# Small_2.net
KiCad netlist of a schematic drawn in EAGLE
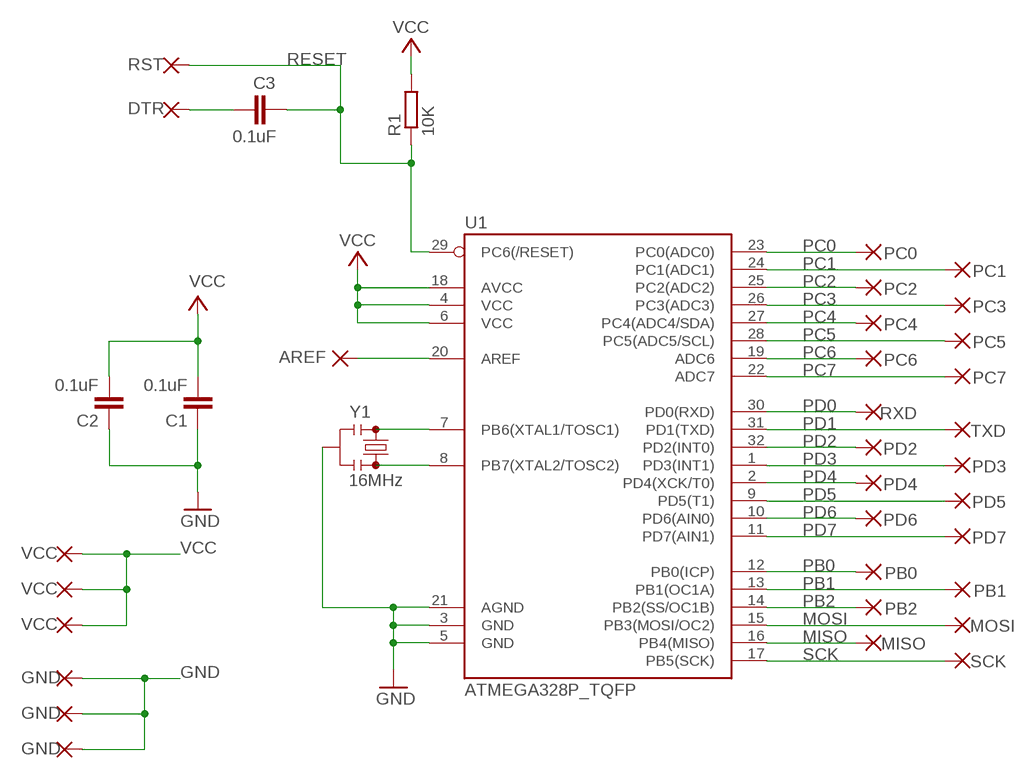
[diagram p0: schematic, sheet 1]

(export (version "E")
  (design (tool "Eeschema 10.0.6"))
  (components
    (comp (ref "AREF")
      (value "1,6/0,8")
      (footprint "eagle-import:1,6_0,8")
      (libsource (lib "eagle-import") (part "1,6/0,8"))
    )
    (comp (ref "C1")
      (value "0.1uF")
      (footprint "eagle-import:C0603")
      (libsource (lib "eagle-import") (part "C-EUC0603"))
    )
    (comp (ref "C2")
      (value "0.1uF")
      (footprint "eagle-import:C0603")
      (libsource (lib "eagle-import") (part "C-EUC0603"))
    )
    (comp (ref "C3")
      (value "0.1uF")
      (footprint "eagle-import:C0603")
      (libsource (lib "eagle-import") (part "C-EUC0603"))
    )
    (comp (ref "DTR")
      (value "1,6/0,8")
      (footprint "eagle-import:1,6_0,8")
      (libsource (lib "eagle-import") (part "1,6/0,8"))
    )
    (comp (ref "DTR1")
      (value "RST")
      (footprint "eagle-import:1,6_0,8")
      (libsource (lib "eagle-import") (part "1,6/0,8"))
    )
    (comp (ref "GND")
      (value "GND")
      (footprint "eagle-import:1,6_0,8")
      (libsource (lib "eagle-import") (part "1,6/0,8"))
    )
    (comp (ref "GND3")
      (value "GND")
      (footprint "eagle-import:1,6_0,8")
      (libsource (lib "eagle-import") (part "1,6/0,8"))
    )
    (comp (ref "GND4")
      (value "GND")
      (footprint "eagle-import:1,6_0,8")
      (libsource (lib "eagle-import") (part "1,6/0,8"))
    )
    (comp (ref "MISO")
      (value "MISO")
      (footprint "eagle-import:1,6_0,8")
      (libsource (lib "eagle-import") (part "1,6/0,8"))
    )
    (comp (ref "MOSI")
      (value "MOSI")
      (footprint "eagle-import:1,6_0,8")
      (libsource (lib "eagle-import") (part "1,6/0,8"))
    )
    (comp (ref "PB0")
      (value "1,6/0,8")
      (footprint "eagle-import:1,6_0,8")
      (libsource (lib "eagle-import") (part "1,6/0,8"))
    )
    (comp (ref "PB1")
      (value "1,6/0,8")
      (footprint "eagle-import:1,6_0,8")
      (libsource (lib "eagle-import") (part "1,6/0,8"))
    )
    (comp (ref "PB2")
      (value "1,6/0,8")
      (footprint "eagle-import:1,6_0,8")
      (libsource (lib "eagle-import") (part "1,6/0,8"))
    )
    (comp (ref "PC0")
      (value "1,6/0,8")
      (footprint "eagle-import:1,6_0,8")
      (libsource (lib "eagle-import") (part "1,6/0,8"))
    )
    (comp (ref "PC1")
      (value "1,6/0,8")
      (footprint "eagle-import:1,6_0,8")
      (libsource (lib "eagle-import") (part "1,6/0,8"))
    )
    (comp (ref "PC2")
      (value "1,6/0,8")
      (footprint "eagle-import:1,6_0,8")
      (libsource (lib "eagle-import") (part "1,6/0,8"))
    )
    (comp (ref "PC3")
      (value "1,6/0,8")
      (footprint "eagle-import:1,6_0,8")
      (libsource (lib "eagle-import") (part "1,6/0,8"))
    )
    (comp (ref "PC4")
      (value "1,6/0,8")
      (footprint "eagle-import:1,6_0,8")
      (libsource (lib "eagle-import") (part "1,6/0,8"))
    )
    (comp (ref "PC5")
      (value "1,6/0,8")
      (footprint "eagle-import:1,6_0,8")
      (libsource (lib "eagle-import") (part "1,6/0,8"))
    )
    (comp (ref "PC6")
      (value "1,6/0,8")
      (footprint "eagle-import:1,6_0,8")
      (libsource (lib "eagle-import") (part "1,6/0,8"))
    )
    (comp (ref "PC7")
      (value "1,6/0,8")
      (footprint "eagle-import:1,6_0,8")
      (libsource (lib "eagle-import") (part "1,6/0,8"))
    )
    (comp (ref "PD2")
      (value "1,6/0,8")
      (footprint "eagle-import:1,6_0,8")
      (libsource (lib "eagle-import") (part "1,6/0,8"))
    )
    (comp (ref "PD3")
      (value "1,6/0,8")
      (footprint "eagle-import:1,6_0,8")
      (libsource (lib "eagle-import") (part "1,6/0,8"))
    )
    (comp (ref "PD4")
      (value "1,6/0,8")
      (footprint "eagle-import:1,6_0,8")
      (libsource (lib "eagle-import") (part "1,6/0,8"))
    )
    (comp (ref "PD5")
      (value "1,6/0,8")
      (footprint "eagle-import:1,6_0,8")
      (libsource (lib "eagle-import") (part "1,6/0,8"))
    )
    (comp (ref "PD6")
      (value "1,6/0,8")
      (footprint "eagle-import:1,6_0,8")
      (libsource (lib "eagle-import") (part "1,6/0,8"))
    )
    (comp (ref "PD7")
      (value "1,6/0,8")
      (footprint "eagle-import:1,6_0,8")
      (libsource (lib "eagle-import") (part "1,6/0,8"))
    )
    (comp (ref "R1")
      (value "10K")
      (footprint "eagle-import:R0603")
      (libsource (lib "eagle-import") (part "R-EU_R0603"))
    )
    (comp (ref "RXD")
      (value "1,6/0,8")
      (footprint "eagle-import:1,6_0,8")
      (libsource (lib "eagle-import") (part "1,6/0,8"))
    )
    (comp (ref "SCK")
      (value "SCK")
      (footprint "eagle-import:1,6_0,8")
      (libsource (lib "eagle-import") (part "1,6/0,8"))
    )
    (comp (ref "TXD")
      (value "1,6/0,8")
      (footprint "eagle-import:1,6_0,8")
      (libsource (lib "eagle-import") (part "1,6/0,8"))
    )
    (comp (ref "U1")
      (value "ATMEGA328P_TQFP")
      (footprint "eagle-import:TQFP32-08")
      (libsource (lib "eagle-import") (part "ATMEGA328P_TQFP"))
    )
    (comp (ref "VCC")
      (value "VCC")
      (footprint "eagle-import:1,6_0,8")
      (libsource (lib "eagle-import") (part "1,6/0,8"))
    )
    (comp (ref "VCC1")
      (value "VCC")
      (footprint "eagle-import:1,6_0,8")
      (libsource (lib "eagle-import") (part "1,6/0,8"))
    )
    (comp (ref "VCC2")
      (value "VCC")
      (footprint "eagle-import:1,6_0,8")
      (libsource (lib "eagle-import") (part "1,6/0,8"))
    )
    (comp (ref "Y1")
      (value "16MHz")
      (footprint "eagle-import:RESONATOR-SMD-3.2X1.3")
      (libsource (lib "eagle-import") (part "RESONATOR-16MHZSMD_3.2X1.3"))
    )
  )
  (nets
    (net (code "1") (name "/MISO") (class "Default")
      (node (ref "MISO") (pin "1") (pinfunction "P_1") (pintype "passive"))
      (node (ref "U1") (pin "16") (pinfunction "PB4(MISO)_16") (pintype "bidirectional"))
    )
    (net (code "2") (name "/MOSI") (class "Default")
      (node (ref "MOSI") (pin "1") (pinfunction "P_1") (pintype "passive"))
      (node (ref "U1") (pin "15") (pinfunction "PB3(MOSI/OC2)_15") (pintype "bidirectional"))
    )
    (net (code "3") (name "/PB0") (class "Default")
      (node (ref "PB0") (pin "1") (pinfunction "P_1") (pintype "passive"))
      (node (ref "U1") (pin "12") (pinfunction "PB0(ICP)_12") (pintype "bidirectional"))
    )
    (net (code "4") (name "/PB1") (class "Default")
      (node (ref "PB1") (pin "1") (pinfunction "P_1") (pintype "passive"))
      (node (ref "U1") (pin "13") (pinfunction "PB1(OC1A)_13") (pintype "bidirectional"))
    )
    (net (code "5") (name "/PB2") (class "Default")
      (node (ref "PB2") (pin "1") (pinfunction "P_1") (pintype "passive"))
      (node (ref "U1") (pin "14") (pinfunction "PB2(SS/OC1B)_14") (pintype "bidirectional"))
    )
    (net (code "6") (name "/PC0") (class "Default")
      (node (ref "PC0") (pin "1") (pinfunction "P_1") (pintype "passive"))
      (node (ref "U1") (pin "23") (pinfunction "PC0(ADC0)_23") (pintype "bidirectional"))
    )
    (net (code "7") (name "/PC1") (class "Default")
      (node (ref "PC1") (pin "1") (pinfunction "P_1") (pintype "passive"))
      (node (ref "U1") (pin "24") (pinfunction "PC1(ADC1)_24") (pintype "bidirectional"))
    )
    (net (code "8") (name "/PC2") (class "Default")
      (node (ref "PC2") (pin "1") (pinfunction "P_1") (pintype "passive"))
      (node (ref "U1") (pin "25") (pinfunction "PC2(ADC2)_25") (pintype "bidirectional"))
    )
    (net (code "9") (name "/PC3") (class "Default")
      (node (ref "PC3") (pin "1") (pinfunction "P_1") (pintype "passive"))
      (node (ref "U1") (pin "26") (pinfunction "PC3(ADC3)_26") (pintype "bidirectional"))
    )
    (net (code "10") (name "/PC4") (class "Default")
      (node (ref "PC4") (pin "1") (pinfunction "P_1") (pintype "passive"))
      (node (ref "U1") (pin "27") (pinfunction "PC4(ADC4/SDA)_27") (pintype "bidirectional"))
    )
    (net (code "11") (name "/PC5") (class "Default")
      (node (ref "PC5") (pin "1") (pinfunction "P_1") (pintype "passive"))
      (node (ref "U1") (pin "28") (pinfunction "PC5(ADC5/SCL)_28") (pintype "bidirectional"))
    )
    (net (code "12") (name "/PC6") (class "Default")
      (node (ref "PC6") (pin "1") (pinfunction "P_1") (pintype "passive"))
      (node (ref "U1") (pin "19") (pinfunction "ADC6_19") (pintype "bidirectional"))
    )
    (net (code "13") (name "/PC7") (class "Default")
      (node (ref "PC7") (pin "1") (pinfunction "P_1") (pintype "passive"))
      (node (ref "U1") (pin "22") (pinfunction "ADC7_22") (pintype "bidirectional"))
    )
    (net (code "14") (name "/PD0") (class "Default")
      (node (ref "RXD") (pin "1") (pinfunction "P_1") (pintype "passive"))
      (node (ref "U1") (pin "30") (pinfunction "PD0(RXD)_30") (pintype "bidirectional"))
    )
    (net (code "15") (name "/PD1") (class "Default")
      (node (ref "TXD") (pin "1") (pinfunction "P_1") (pintype "passive"))
      (node (ref "U1") (pin "31") (pinfunction "PD1(TXD)_31") (pintype "bidirectional"))
    )
    (net (code "16") (name "/PD2") (class "Default")
      (node (ref "PD2") (pin "1") (pinfunction "P_1") (pintype "passive"))
      (node (ref "U1") (pin "32") (pinfunction "PD2(INT0)_32") (pintype "bidirectional"))
    )
    (net (code "17") (name "/PD3") (class "Default")
      (node (ref "PD3") (pin "1") (pinfunction "P_1") (pintype "passive"))
      (node (ref "U1") (pin "1") (pinfunction "PD3(INT1)_1") (pintype "bidirectional"))
    )
    (net (code "18") (name "/PD4") (class "Default")
      (node (ref "PD4") (pin "1") (pinfunction "P_1") (pintype "passive"))
      (node (ref "U1") (pin "2") (pinfunction "PD4(XCK/T0)_2") (pintype "bidirectional"))
    )
    (net (code "19") (name "/PD5") (class "Default")
      (node (ref "PD5") (pin "1") (pinfunction "P_1") (pintype "passive"))
      (node (ref "U1") (pin "9") (pinfunction "PD5(T1)_9") (pintype "bidirectional"))
    )
    (net (code "20") (name "/PD6") (class "Default")
      (node (ref "PD6") (pin "1") (pinfunction "P_1") (pintype "passive"))
      (node (ref "U1") (pin "10") (pinfunction "PD6(AIN0)_10") (pintype "bidirectional"))
    )
    (net (code "21") (name "/PD7") (class "Default")
      (node (ref "PD7") (pin "1") (pinfunction "P_1") (pintype "passive"))
      (node (ref "U1") (pin "11") (pinfunction "PD7(AIN1)_11") (pintype "bidirectional"))
    )
    (net (code "22") (name "/RESET") (class "Default")
      (node (ref "C3") (pin "2") (pinfunction "2_2") (pintype "passive"))
      (node (ref "DTR1") (pin "1") (pinfunction "P_1") (pintype "passive"))
      (node (ref "R1") (pin "1") (pinfunction "1_1") (pintype "passive"))
      (node (ref "U1") (pin "29") (pinfunction "PC6(/RESET)_29") (pintype "bidirectional"))
    )
    (net (code "23") (name "/SCK") (class "Default")
      (node (ref "SCK") (pin "1") (pinfunction "P_1") (pintype "passive"))
      (node (ref "U1") (pin "17") (pinfunction "PB5(SCK)_17") (pintype "bidirectional"))
    )
    (net (code "24") (name "GND") (class "Default")
      (node (ref "C1") (pin "1") (pinfunction "1_1") (pintype "passive"))
      (node (ref "C2") (pin "1") (pinfunction "1_1") (pintype "passive"))
      (node (ref "GND") (pin "1") (pinfunction "P_1") (pintype "passive"))
      (node (ref "GND3") (pin "1") (pinfunction "P_1") (pintype "passive"))
      (node (ref "GND4") (pin "1") (pinfunction "P_1") (pintype "passive"))
      (node (ref "U1") (pin "21") (pinfunction "AGND_21") (pintype "bidirectional"))
      (node (ref "U1") (pin "3") (pinfunction "GND_3") (pintype "bidirectional"))
      (node (ref "U1") (pin "5") (pinfunction "GND_5") (pintype "bidirectional"))
      (node (ref "Y1") (pin "2") (pinfunction "2_2") (pintype "passive"))
    )
    (net (code "25") (name "Net-(AREF-P)") (class "Default")
      (node (ref "AREF") (pin "1") (pinfunction "P_1") (pintype "passive"))
      (node (ref "U1") (pin "20") (pinfunction "AREF_20") (pintype "bidirectional"))
    )
    (net (code "26") (name "Net-(DTR-P)") (class "Default")
      (node (ref "C3") (pin "1") (pinfunction "1_1") (pintype "passive"))
      (node (ref "DTR") (pin "1") (pinfunction "P_1") (pintype "passive"))
    )
    (net (code "27") (name "Net-(U1-PB6(XTAL1{slash}TOSC1))") (class "Default")
      (node (ref "U1") (pin "7") (pinfunction "PB6(XTAL1/TOSC1)_7") (pintype "bidirectional"))
      (node (ref "Y1") (pin "1") (pinfunction "1_1") (pintype "passive"))
    )
    (net (code "28") (name "Net-(U1-PB7(XTAL2{slash}TOSC2))") (class "Default")
      (node (ref "U1") (pin "8") (pinfunction "PB7(XTAL2/TOSC2)_8") (pintype "bidirectional"))
      (node (ref "Y1") (pin "3") (pinfunction "3_3") (pintype "passive"))
    )
    (net (code "29") (name "VCC") (class "Default")
      (node (ref "C1") (pin "2") (pinfunction "2_2") (pintype "passive"))
      (node (ref "C2") (pin "2") (pinfunction "2_2") (pintype "passive"))
      (node (ref "R1") (pin "2") (pinfunction "2_2") (pintype "passive"))
      (node (ref "U1") (pin "18") (pinfunction "AVCC_18") (pintype "bidirectional"))
      (node (ref "U1") (pin "4") (pinfunction "VCC_4") (pintype "bidirectional"))
      (node (ref "U1") (pin "6") (pinfunction "VCC_6") (pintype "bidirectional"))
      (node (ref "VCC") (pin "1") (pinfunction "P_1") (pintype "passive"))
      (node (ref "VCC1") (pin "1") (pinfunction "P_1") (pintype "passive"))
      (node (ref "VCC2") (pin "1") (pinfunction "P_1") (pintype "passive"))
    )
  )
)
